# sensor_board4.net
KiCad netlist of a schematic drawn in EAGLE
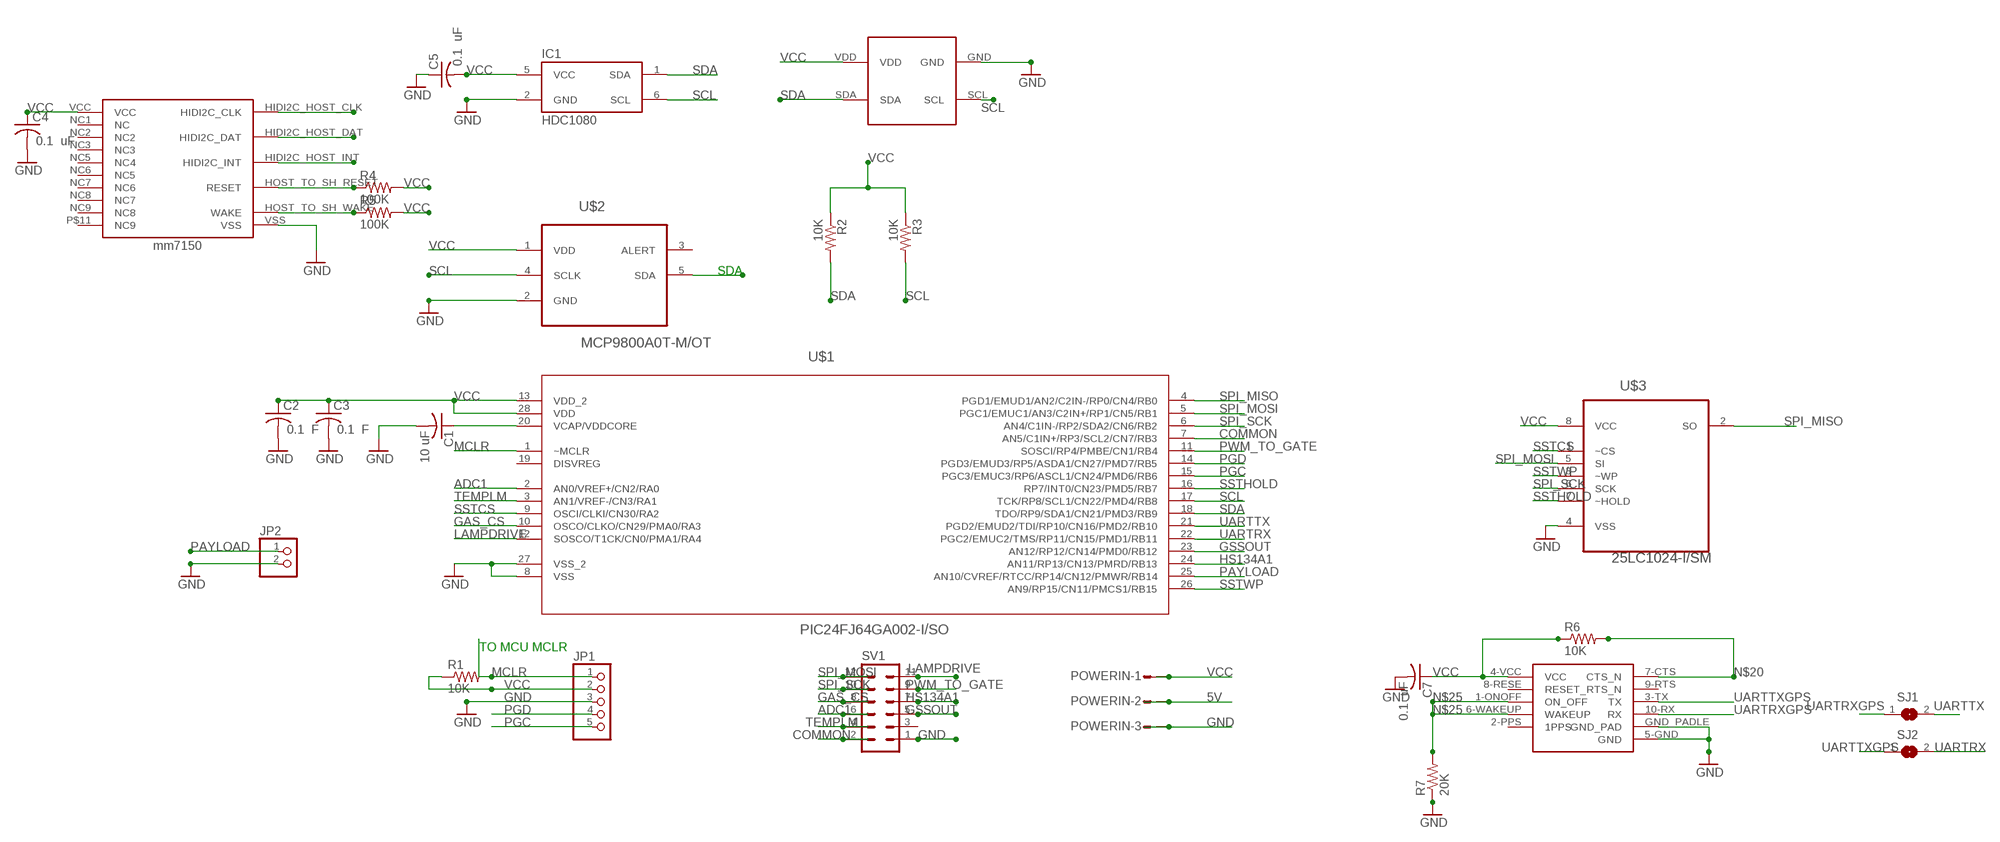
[diagram p0: schematic, sheet 1]

(export (version "E")
  (design (tool "Eeschema 10.0.6"))
  (components
    (comp (ref "C1")
      (value "10 uF")
      (footprint "eagle-import:C0805")
      (libsource (lib "eagle-import") (part "C-USC0805"))
    )
    (comp (ref "C2")
      (value "0.1 F")
      (footprint "eagle-import:C0805")
      (libsource (lib "eagle-import") (part "C-USC0805"))
    )
    (comp (ref "C3")
      (value "0.1 F")
      (footprint "eagle-import:C0805")
      (libsource (lib "eagle-import") (part "C-USC0805"))
    )
    (comp (ref "C4")
      (value "0.1 uF")
      (footprint "eagle-import:C0805")
      (libsource (lib "eagle-import") (part "C-USC0805"))
    )
    (comp (ref "C5")
      (value "0.1 uF")
      (footprint "eagle-import:C0805")
      (libsource (lib "eagle-import") (part "C-USC0805"))
    )
    (comp (ref "C7")
      (value "0.1 uF")
      (footprint "eagle-import:C0805")
      (libsource (lib "eagle-import") (part "C-USC0805"))
    )
    (comp (ref "IC1")
      (value "HDC1080")
      (footprint "eagle-import:WSON6")
      (libsource (lib "eagle-import") (part "HDC1080"))
    )
    (comp (ref "JP1")
      (value "PINHD-1X5")
      (footprint "eagle-import:1X05")
      (libsource (lib "eagle-import") (part "PINHD-1X5"))
    )
    (comp (ref "JP2")
      (value "PINHD-1X2")
      (footprint "eagle-import:1X02")
      (libsource (lib "eagle-import") (part "PINHD-1X2"))
    )
    (comp (ref "POWERIN")
      (value "L03P")
      (footprint "eagle-import:L03P")
      (libsource (lib "eagle-import") (part "L03P"))
    )
    (comp (ref "R1")
      (value "10K")
      (footprint "eagle-import:M0805")
      (libsource (lib "eagle-import") (part "R-US_M0805"))
    )
    (comp (ref "R2")
      (value "10K")
      (footprint "eagle-import:M0805")
      (libsource (lib "eagle-import") (part "R-US_M0805"))
    )
    (comp (ref "R3")
      (value "10K")
      (footprint "eagle-import:M0805")
      (libsource (lib "eagle-import") (part "R-US_M0805"))
    )
    (comp (ref "R4")
      (value "100K")
      (footprint "eagle-import:M0805")
      (libsource (lib "eagle-import") (part "R-US_M0805"))
    )
    (comp (ref "R5")
      (value "100K")
      (footprint "eagle-import:M0805")
      (libsource (lib "eagle-import") (part "R-US_M0805"))
    )
    (comp (ref "R6")
      (value "10K")
      (footprint "eagle-import:M0805")
      (libsource (lib "eagle-import") (part "R-US_M0805"))
    )
    (comp (ref "R7")
      (value "20K")
      (footprint "eagle-import:M0805")
      (libsource (lib "eagle-import") (part "R-US_M0805"))
    )
    (comp (ref "SJ1") (value "SJ") (footprint "eagle-import:SJ") (libsource (lib "eagle-import") (part "SJ")))
    (comp (ref "SJ2") (value "SJ") (footprint "eagle-import:SJ") (libsource (lib "eagle-import") (part "SJ")))
    (comp (ref "SV1")
      (value "MA06-2")
      (footprint "eagle-import:MA06-2")
      (libsource (lib "eagle-import") (part "MA06-2"))
    )
    (comp (ref "U$1")
      (value "PIC24FJ64GA002-I/SO")
      (footprint "eagle-import:SOIC127P1030X265-28N")
      (libsource (lib "eagle-import") (part "PIC24FJ64GA002-I/SO"))
    )
    (comp (ref "U$2")
      (value "MCP9800A0T-M/OT")
      (footprint "eagle-import:SOT95P280X145-5N")
      (libsource (lib "eagle-import") (part "MCP9800A0T-M/OT"))
    )
    (comp (ref "U$3")
      (value "25LC1024-I/SM")
      (footprint "eagle-import:SOIC127P794X203-8N")
      (libsource (lib "eagle-import") (part "25LC1024-I/SM"))
    )
    (comp (ref "U$4")
      (value "MS5637")
      (footprint "eagle-import:MS5637")
      (libsource (lib "eagle-import") (part "MS5637"))
    )
    (comp (ref "U$5")
      (value "ORG1411")
      (footprint "eagle-import:LGA")
      (libsource (lib "eagle-import") (part "ORG1411"))
    )
    (comp (ref "U$6")
      (value "MM7150")
      (footprint "eagle-import:MM7150-QFN16")
      (libsource (lib "eagle-import") (part "MM7150"))
    )
  )
  (nets
    (net (code "1") (name "/5V") (class "Default")
      (node (ref "POWERIN") (pin "2") (pinfunction "S_2") (pintype "passive"))
    )
    (net (code "2") (name "/ADC1") (class "Default")
      (node (ref "SV1") (pin "6") (pinfunction "6_6") (pintype "passive"))
      (node (ref "U$1") (pin "2") (pinfunction "AN0/VREF+/CN2/RA0_2") (pintype "bidirectional"))
    )
    (net (code "3") (name "/COMMON") (class "Default")
      (node (ref "SV1") (pin "2") (pinfunction "2_2") (pintype "passive"))
      (node (ref "U$1") (pin "7") (pinfunction "AN5/C1IN+/RP3/SCL2/CN7/RB3_7") (pintype "bidirectional"))
    )
    (net (code "4") (name "/GAS_CS") (class "Default")
      (node (ref "SV1") (pin "8") (pinfunction "8_8") (pintype "passive"))
      (node (ref "U$1") (pin "10") (pinfunction "OSCO/CLKO/CN29/PMA0/RA3_10") (pintype "bidirectional"))
    )
    (net (code "5") (name "/GSSOUT") (class "Default")
      (node (ref "SV1") (pin "5") (pinfunction "5_5") (pintype "passive"))
      (node (ref "U$1") (pin "23") (pinfunction "AN12/RP12/CN14/PMD0/RB12_23") (pintype "bidirectional"))
    )
    (net (code "6") (name "/HS134A1") (class "Default")
      (node (ref "SV1") (pin "7") (pinfunction "7_7") (pintype "passive"))
      (node (ref "U$1") (pin "24") (pinfunction "AN11/RP13/CN13/PMRD/RB13_24") (pintype "bidirectional"))
    )
    (net (code "7") (name "/LAMPDRIVE") (class "Default")
      (node (ref "SV1") (pin "11") (pinfunction "11_11") (pintype "passive"))
      (node (ref "U$1") (pin "12") (pinfunction "SOSCO/T1CK/CN0/PMA1/RA4_12") (pintype "bidirectional"))
    )
    (net (code "8") (name "/MCLR") (class "Default")
      (node (ref "JP1") (pin "1") (pinfunction "1_1") (pintype "passive"))
      (node (ref "R1") (pin "2") (pinfunction "2_2") (pintype "passive"))
      (node (ref "U$1") (pin "1") (pinfunction "~{MCLR}_1") (pintype "input"))
    )
    (net (code "9") (name "/N$20") (class "Default")
      (node (ref "R6") (pin "2") (pinfunction "2_2") (pintype "passive"))
      (node (ref "U$5") (pin "7-CTS") (pinfunction "CTS_N_7-CTS") (pintype "bidirectional"))
    )
    (net (code "10") (name "/N$25") (class "Default")
      (node (ref "R7") (pin "2") (pinfunction "2_2") (pintype "passive"))
      (node (ref "U$5") (pin "1-ONOFF") (pinfunction "ON_OFF_1-ONOFF") (pintype "bidirectional"))
      (node (ref "U$5") (pin "6-WAKEUP") (pinfunction "WAKEUP_6-WAKEUP") (pintype "bidirectional"))
    )
    (net (code "11") (name "/PAYLOAD") (class "Default")
      (node (ref "JP2") (pin "1") (pinfunction "1_1") (pintype "passive"))
      (node (ref "U$1") (pin "25") (pinfunction "AN10/CVREF/RTCC/RP14/CN12/PMWR/RB14_25") (pintype "bidirectional"))
    )
    (net (code "12") (name "/PGC") (class "Default")
      (node (ref "JP1") (pin "5") (pinfunction "5_5") (pintype "passive"))
      (node (ref "U$1") (pin "15") (pinfunction "PGC3/EMUC3/RP6/ASCL1/CN24/PMD6/RB6_15") (pintype "bidirectional"))
    )
    (net (code "13") (name "/PGD") (class "Default")
      (node (ref "JP1") (pin "4") (pinfunction "4_4") (pintype "passive"))
      (node (ref "U$1") (pin "14") (pinfunction "PGD3/EMUD3/RP5/ASDA1/CN27/PMD7/RB5_14") (pintype "bidirectional"))
    )
    (net (code "14") (name "/PWM_TO_GATE") (class "Default")
      (node (ref "SV1") (pin "9") (pinfunction "9_9") (pintype "passive"))
      (node (ref "U$1") (pin "11") (pinfunction "SOSCI/RP4/PMBE/CN1/RB4_11") (pintype "bidirectional"))
    )
    (net (code "15") (name "/SCL") (class "Default")
      (node (ref "IC1") (pin "6") (pinfunction "SCL_6") (pintype "bidirectional"))
      (node (ref "R3") (pin "2") (pinfunction "2_2") (pintype "passive"))
      (node (ref "U$1") (pin "17") (pinfunction "TCK/RP8/SCL1/CN22/PMD4/RB8_17") (pintype "bidirectional"))
      (node (ref "U$2") (pin "4") (pinfunction "SCLK_4") (pintype "input"))
      (node (ref "U$4") (pin "SCL") (pinfunction "SCL_SCL") (pintype "bidirectional"))
      (node (ref "U$6") (pin "HIDI2C_HOST_CLK") (pinfunction "HIDI2C_CLK_HIDI2C_HOST_CLK") (pintype "bidirectional"))
    )
    (net (code "16") (name "/SDA") (class "Default")
      (node (ref "IC1") (pin "1") (pinfunction "SDA_1") (pintype "bidirectional"))
      (node (ref "R2") (pin "2") (pinfunction "2_2") (pintype "passive"))
      (node (ref "U$1") (pin "18") (pinfunction "TDO/RP9/SDA1/CN21/PMD3/RB9_18") (pintype "bidirectional"))
      (node (ref "U$2") (pin "5") (pinfunction "SDA_5") (pintype "bidirectional"))
      (node (ref "U$4") (pin "SDA") (pinfunction "SDA_SDA") (pintype "bidirectional"))
      (node (ref "U$6") (pin "HIDI2C_HOST_DAT") (pinfunction "HIDI2C_DAT_HIDI2C_HOST_DAT") (pintype "bidirectional"))
    )
    (net (code "17") (name "/SPI_MISO") (class "Default")
      (node (ref "U$1") (pin "4") (pinfunction "PGD1/EMUD1/AN2/C2IN-/RP0/CN4/RB0_4") (pintype "bidirectional"))
      (node (ref "U$3") (pin "2") (pinfunction "SO_2") (pintype "output"))
    )
    (net (code "18") (name "/SPI_MOSI") (class "Default")
      (node (ref "SV1") (pin "12") (pinfunction "12_12") (pintype "passive"))
      (node (ref "U$1") (pin "5") (pinfunction "PGC1/EMUC1/AN3/C2IN+/RP1/CN5/RB1_5") (pintype "bidirectional"))
      (node (ref "U$3") (pin "5") (pinfunction "SI_5") (pintype "input"))
    )
    (net (code "19") (name "/SPI_SCK") (class "Default")
      (node (ref "SV1") (pin "10") (pinfunction "10_10") (pintype "passive"))
      (node (ref "U$1") (pin "6") (pinfunction "AN4/C1IN-/RP2/SDA2/CN6/RB2_6") (pintype "bidirectional"))
      (node (ref "U$3") (pin "6") (pinfunction "SCK_6") (pintype "input"))
    )
    (net (code "20") (name "/SSTCS") (class "Default")
      (node (ref "U$1") (pin "9") (pinfunction "OSCI/CLKI/CN30/RA2_9") (pintype "bidirectional"))
      (node (ref "U$3") (pin "1") (pinfunction "~{CS}_1") (pintype "input"))
    )
    (net (code "21") (name "/SSTHOLD") (class "Default")
      (node (ref "U$1") (pin "16") (pinfunction "RP7/INT0/CN23/PMD5/RB7_16") (pintype "bidirectional"))
      (node (ref "U$3") (pin "7") (pinfunction "~{HOLD}_7") (pintype "input"))
    )
    (net (code "22") (name "/SSTWP") (class "Default")
      (node (ref "U$1") (pin "26") (pinfunction "AN9/RP15/CN11/PMCS1/RB15_26") (pintype "bidirectional"))
      (node (ref "U$3") (pin "3") (pinfunction "~{WP}_3") (pintype "input"))
    )
    (net (code "23") (name "/TEMPLM") (class "Default")
      (node (ref "SV1") (pin "4") (pinfunction "4_4") (pintype "passive"))
      (node (ref "U$1") (pin "3") (pinfunction "AN1/VREF-/CN3/RA1_3") (pintype "bidirectional"))
    )
    (net (code "24") (name "/UARTRX") (class "Default")
      (node (ref "SJ2") (pin "2") (pinfunction "2_2") (pintype "passive"))
      (node (ref "U$1") (pin "22") (pinfunction "PGC2/EMUC2/TMS/RP11/CN15/PMD1/RB11_22") (pintype "bidirectional"))
    )
    (net (code "25") (name "/UARTRXGPS") (class "Default")
      (node (ref "SJ1") (pin "1") (pinfunction "1_1") (pintype "passive"))
      (node (ref "U$5") (pin "10-RX") (pinfunction "RX_10-RX") (pintype "bidirectional"))
    )
    (net (code "26") (name "/UARTTX") (class "Default")
      (node (ref "SJ1") (pin "2") (pinfunction "2_2") (pintype "passive"))
      (node (ref "U$1") (pin "21") (pinfunction "PGD2/EMUD2/TDI/RP10/CN16/PMD2/RB10_21") (pintype "bidirectional"))
    )
    (net (code "27") (name "/UARTTXGPS") (class "Default")
      (node (ref "SJ2") (pin "1") (pinfunction "1_1") (pintype "passive"))
      (node (ref "U$5") (pin "3-TX") (pinfunction "TX_3-TX") (pintype "bidirectional"))
    )
    (net (code "28") (name "/VCC") (class "Default")
      (node (ref "C2") (pin "1") (pinfunction "1_1") (pintype "passive"))
      (node (ref "C3") (pin "1") (pinfunction "1_1") (pintype "passive"))
      (node (ref "C4") (pin "1") (pinfunction "1_1") (pintype "passive"))
      (node (ref "C5") (pin "2") (pinfunction "2_2") (pintype "passive"))
      (node (ref "C7") (pin "1") (pinfunction "1_1") (pintype "passive"))
      (node (ref "IC1") (pin "5") (pinfunction "VCC_5") (pintype "power_in"))
      (node (ref "JP1") (pin "2") (pinfunction "2_2") (pintype "passive"))
      (node (ref "POWERIN") (pin "1") (pinfunction "S_1") (pintype "passive"))
      (node (ref "R1") (pin "1") (pinfunction "1_1") (pintype "passive"))
      (node (ref "R2") (pin "1") (pinfunction "1_1") (pintype "passive"))
      (node (ref "R3") (pin "1") (pinfunction "1_1") (pintype "passive"))
      (node (ref "R4") (pin "2") (pinfunction "2_2") (pintype "passive"))
      (node (ref "R5") (pin "2") (pinfunction "2_2") (pintype "passive"))
      (node (ref "R6") (pin "1") (pinfunction "1_1") (pintype "passive"))
      (node (ref "U$1") (pin "13") (pinfunction "VDD_2_13") (pintype "power_in"))
      (node (ref "U$1") (pin "28") (pinfunction "VDD_28") (pintype "power_in"))
      (node (ref "U$2") (pin "1") (pinfunction "VDD_1") (pintype "power_in"))
      (node (ref "U$3") (pin "8") (pinfunction "VCC_8") (pintype "power_in"))
      (node (ref "U$4") (pin "VDD") (pinfunction "VDD_VDD") (pintype "bidirectional"))
      (node (ref "U$5") (pin "4-VCC") (pinfunction "VCC_4-VCC") (pintype "bidirectional"))
      (node (ref "U$6") (pin "VCC") (pinfunction "VCC_VCC") (pintype "bidirectional"))
    )
    (net (code "29") (name "GND") (class "Default")
      (node (ref "C1") (pin "2") (pinfunction "2_2") (pintype "passive"))
      (node (ref "C2") (pin "2") (pinfunction "2_2") (pintype "passive"))
      (node (ref "C3") (pin "2") (pinfunction "2_2") (pintype "passive"))
      (node (ref "C4") (pin "2") (pinfunction "2_2") (pintype "passive"))
      (node (ref "C5") (pin "1") (pinfunction "1_1") (pintype "passive"))
      (node (ref "C7") (pin "2") (pinfunction "2_2") (pintype "passive"))
      (node (ref "IC1") (pin "2") (pinfunction "GND_2") (pintype "power_in"))
      (node (ref "JP1") (pin "3") (pinfunction "3_3") (pintype "passive"))
      (node (ref "JP2") (pin "2") (pinfunction "2_2") (pintype "passive"))
      (node (ref "POWERIN") (pin "3") (pinfunction "S_3") (pintype "passive"))
      (node (ref "R7") (pin "1") (pinfunction "1_1") (pintype "passive"))
      (node (ref "SV1") (pin "1") (pinfunction "1_1") (pintype "passive"))
      (node (ref "U$1") (pin "27") (pinfunction "VSS_2_27") (pintype "power_in"))
      (node (ref "U$1") (pin "8") (pinfunction "VSS_8") (pintype "power_in"))
      (node (ref "U$2") (pin "2") (pinfunction "GND_2") (pintype "passive"))
      (node (ref "U$3") (pin "4") (pinfunction "VSS_4") (pintype "passive"))
      (node (ref "U$4") (pin "GND") (pinfunction "GND_GND") (pintype "bidirectional"))
      (node (ref "U$5") (pin "5-GND") (pinfunction "GND_5-GND") (pintype "bidirectional"))
      (node (ref "U$5") (pin "GND_PADLE") (pinfunction "GND_PAD_GND_PADLE") (pintype "bidirectional"))
      (node (ref "U$6") (pin "VSS") (pinfunction "VSS_VSS") (pintype "bidirectional"))
    )
    (net (code "30") (name "Net-(U$1-VCAP{slash}VDDCORE)") (class "Default")
      (node (ref "C1") (pin "1") (pinfunction "1_1") (pintype "passive"))
      (node (ref "U$1") (pin "20") (pinfunction "VCAP/VDDCORE_20") (pintype "power_in"))
    )
    (net (code "31") (name "Net-(U$6-RESET)") (class "Default")
      (node (ref "R4") (pin "1") (pinfunction "1_1") (pintype "passive"))
      (node (ref "U$6") (pin "HOST_TO_SH_RESET") (pinfunction "RESET_HOST_TO_SH_RESET") (pintype "bidirectional"))
    )
    (net (code "32") (name "Net-(U$6-WAKE)") (class "Default")
      (node (ref "R5") (pin "1") (pinfunction "1_1") (pintype "passive"))
      (node (ref "U$6") (pin "HOST_TO_SH_WAKE") (pinfunction "WAKE_HOST_TO_SH_WAKE") (pintype "bidirectional"))
    )
    (net (code "33") (name "unconnected-(SV1-Pad3)") (class "Default")
      (node (ref "SV1") (pin "3") (pinfunction "3_3") (pintype "passive"))
    )
    (net (code "34") (name "unconnected-(U$1-DISVREG-Pad19)") (class "Default")
      (node (ref "U$1") (pin "19") (pinfunction "DISVREG_19") (pintype "passive"))
    )
    (net (code "35") (name "unconnected-(U$2-ALERT-Pad3)") (class "Default")
      (node (ref "U$2") (pin "3") (pinfunction "ALERT_3") (pintype "output"))
    )
    (net (code "36") (name "unconnected-(U$5-1PPS-Pad2-PPS)") (class "Default")
      (node (ref "U$5") (pin "2-PPS") (pinfunction "1PPS_2-PPS") (pintype "bidirectional"))
    )
    (net (code "37") (name "unconnected-(U$5-RESET_-Pad8-RESE)") (class "Default")
      (node (ref "U$5") (pin "8-RESE") (pinfunction "RESET__8-RESE") (pintype "bidirectional"))
    )
    (net (code "38") (name "unconnected-(U$5-RTS_N-Pad9-RTS)") (class "Default")
      (node (ref "U$5") (pin "9-RTS") (pinfunction "RTS_N_9-RTS") (pintype "bidirectional"))
    )
    (net (code "39") (name "unconnected-(U$6-HIDI2C_INT-PadHIDI2C_HOST_INT)") (class "Default")
      (node (ref "U$6") (pin "HIDI2C_HOST_INT") (pinfunction "HIDI2C_INT_HIDI2C_HOST_INT") (pintype "bidirectional"))
    )
    (net (code "40") (name "unconnected-(U$6-NC-PadNC1)") (class "Default")
      (node (ref "U$6") (pin "NC1") (pinfunction "NC_NC1") (pintype "bidirectional"))
    )
    (net (code "41") (name "unconnected-(U$6-NC4-PadNC5)") (class "Default")
      (node (ref "U$6") (pin "NC5") (pinfunction "NC4_NC5") (pintype "bidirectional"))
    )
    (net (code "42") (name "unconnected-(U$6-NC5-PadNC6)") (class "Default")
      (node (ref "U$6") (pin "NC6") (pinfunction "NC5_NC6") (pintype "bidirectional"))
    )
    (net (code "43") (name "unconnected-(U$6-NC6-PadNC7)") (class "Default")
      (node (ref "U$6") (pin "NC7") (pinfunction "NC6_NC7") (pintype "bidirectional"))
    )
    (net (code "44") (name "unconnected-(U$6-NC7-PadNC8)") (class "Default")
      (node (ref "U$6") (pin "NC8") (pinfunction "NC7_NC8") (pintype "bidirectional"))
    )
    (net (code "45") (name "unconnected-(U$6-NC8-PadNC9)") (class "Default")
      (node (ref "U$6") (pin "NC9") (pinfunction "NC8_NC9") (pintype "bidirectional"))
    )
    (net (code "46") (name "unconnected-(U$6-NC9-PadP$11)") (class "Default")
      (node (ref "U$6") (pin "P$11") (pinfunction "NC9_P$11") (pintype "bidirectional"))
    )
    (net (code "47") (name "unconnected-(U$6-PadNC2)") (class "Default")
      (node (ref "U$6") (pin "NC2") (pinfunction "NC2_NC2") (pintype "bidirectional"))
    )
    (net (code "48") (name "unconnected-(U$6-PadNC3)") (class "Default")
      (node (ref "U$6") (pin "NC3") (pinfunction "NC3_NC3") (pintype "bidirectional"))
    )
  )
)
